# POWER.net
KiCad netlist of a schematic drawn in Altium Designer
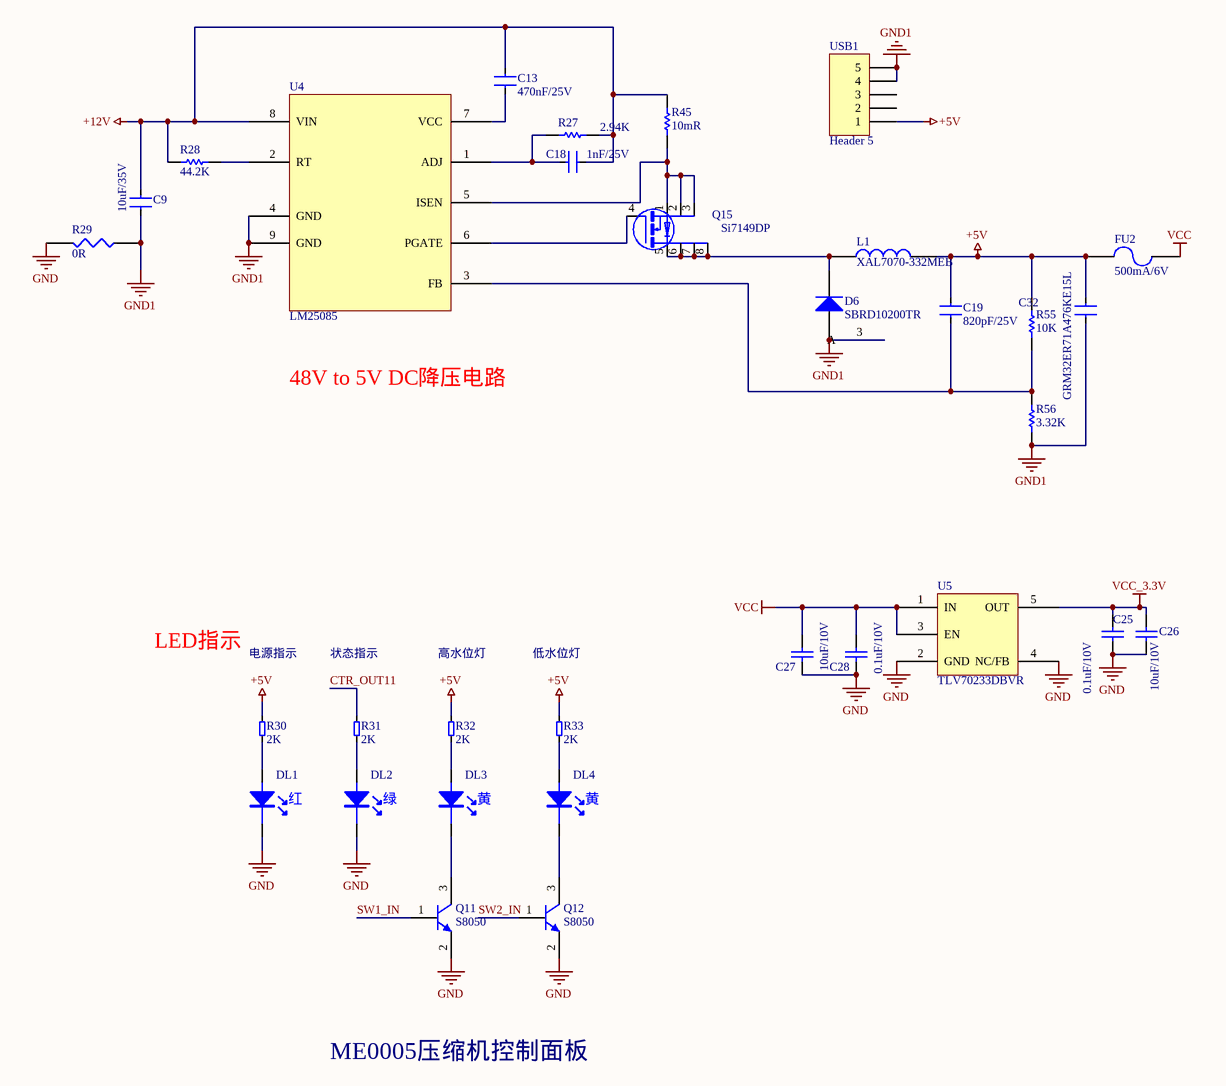
[diagram p0: POWER.SchDoc]

(export (version "E")
  (design (tool "Eeschema 10.0.6"))
  (components
    (comp (ref "C9")
      (value "10uF/35V")
      (footprint "1210C")
      (description "CCX85-103")
      (libsource (lib "无极性电容") (part "0.01UF"))
    )
    (comp (ref "C13")
      (value "470nF/25V")
      (footprint "0603C")
      (description "CCX85-103")
      (libsource (lib "无极性电容") (part "0.01UF"))
    )
    (comp (ref "C18")
      (value "1nF/25V")
      (footprint "0603C")
      (description "CCX85-103")
      (libsource (lib "无极性电容") (part "0.01UF"))
    )
    (comp (ref "C19")
      (value "820pF/25V")
      (footprint "0603C")
      (description "CCX85-103")
      (libsource (lib "无极性电容") (part "0.01UF"))
    )
    (comp (ref "C25")
      (value "0.1uF/10V")
      (footprint "0603C")
      (description "Capacitor")
      (fields (field (name "PUBLISHER") "Altium Limited"))
      (libsource (lib "Miscellaneous Devices") (part "Cap"))
    )
    (comp (ref "C26")
      (value "10uF/10V")
      (footprint "0603C")
      (description "Capacitor")
      (fields (field (name "PUBLISHER") "Altium Limited"))
      (libsource (lib "Miscellaneous Devices") (part "Cap"))
    )
    (comp (ref "C27")
      (value "10uF/10V")
      (footprint "0603C")
      (description "Capacitor")
      (fields (field (name "PUBLISHER") "Altium Limited"))
      (libsource (lib "Miscellaneous Devices") (part "Cap"))
    )
    (comp (ref "C28")
      (value "0.1uF/10V")
      (footprint "0603C")
      (description "Capacitor")
      (fields (field (name "PUBLISHER") "Altium Limited"))
      (libsource (lib "Miscellaneous Devices") (part "Cap"))
    )
    (comp (ref "C32")
      (value "GRM32ER71A476KE15L")
      (footprint "1210C")
      (description "CCX85-103")
      (libsource (lib "无极性电容") (part "0.01UF"))
    )
    (comp (ref "D6")
      (value "SBRD10200TR")
      (footprint "TO228P970-3N")
      (description "Default Diode")
      (fields (field (name "PUBLISHER") "Altium Limited"))
      (libsource (lib "SM") (part "Diode_2"))
    )
    (comp (ref "DL1")
      (value "红")
      (footprint "LED-3")
      (description "CP-L-7113SRD-D")
      (libsource (lib "光电器件") (part "L-7113SRD-D"))
    )
    (comp (ref "DL2")
      (value "绿")
      (footprint "LED-3")
      (description "CP-L-7113SRD-D")
      (libsource (lib "光电器件") (part "L-7113SRD-D"))
    )
    (comp (ref "DL3")
      (value "黄")
      (footprint "LED-3")
      (description "CP-L-7113SRD-D")
      (libsource (lib "光电器件") (part "L-7113SRD-D"))
    )
    (comp (ref "DL4")
      (value "黄")
      (footprint "LED-3")
      (description "CP-L-7113SRD-D")
      (libsource (lib "光电器件") (part "L-7113SRD-D"))
    )
    (comp (ref "FU2")
      (value "500mA/6V")
      (footprint "F0805")
      (description "Fuse")
      (libsource (lib "SM") (part "FUSE2"))
    )
    (comp (ref "L1") (value "XAL7070-332MEB") (footprint "XAL7070") (libsource (lib "*") (part "INDUCTOR")))
    (comp (ref "Q11")
      (value "S8050")
      (footprint "SOT23-3")
      (description "NPN Bipolar Transistor")
      (fields (field (name "PUBLISHER") "Altium Limited"))
      (libsource (lib "Miscellaneous Devices") (part "NPN"))
    )
    (comp (ref "Q12")
      (value "S8050")
      (footprint "SOT23-3")
      (description "NPN Bipolar Transistor")
      (fields (field (name "PUBLISHER") "Altium Limited"))
      (libsource (lib "Miscellaneous Devices") (part "NPN"))
    )
    (comp (ref "Q15")
      (value "Si7149DP")
      (footprint "PowerPAK SO-8")
      (description "Si4004DY")
      (libsource (lib "Schlib_20110825") (part "Si4004DY"))
    )
    (comp (ref "R27")
      (value "2.94K")
      (footprint "0603R")
      (description "Semiconductor Resistor")
      (fields (field (name "PUBLISHER") "Altium Limited"))
      (libsource (lib "Miscellaneous Devices") (part "Res Semi"))
    )
    (comp (ref "R28")
      (value "44.2K")
      (footprint "0603R")
      (description "Semiconductor Resistor")
      (fields (field (name "PUBLISHER") "Altium Limited"))
      (libsource (lib "Miscellaneous Devices") (part "Res Semi"))
    )
    (comp (ref "R29") (value "0R") (footprint "0805R") (libsource (lib "其他电阻") (part "RES1")))
    (comp (ref "R30")
      (value "2K")
      (footprint "0805R")
      (description "CR85-102J")
      (libsource (lib "SMD电阻") (part "1K"))
    )
    (comp (ref "R31")
      (value "2K")
      (footprint "0805R")
      (description "CR85-102J")
      (libsource (lib "SMD电阻") (part "1K"))
    )
    (comp (ref "R32")
      (value "2K")
      (footprint "0805R")
      (description "CR85-102J")
      (libsource (lib "SMD电阻") (part "1K"))
    )
    (comp (ref "R33")
      (value "2K")
      (footprint "0805R")
      (description "CR85-102J")
      (libsource (lib "SMD电阻") (part "1K"))
    )
    (comp (ref "R45")
      (value "10mR")
      (footprint "1206R")
      (description "Semiconductor Resistor")
      (fields (field (name "PUBLISHER") "Altium Limited"))
      (libsource (lib "Miscellaneous Devices") (part "Res Semi"))
    )
    (comp (ref "R55")
      (value "10K")
      (footprint "0603R")
      (description "Semiconductor Resistor")
      (fields (field (name "PUBLISHER") "Altium Limited"))
      (libsource (lib "Miscellaneous Devices") (part "Res Semi"))
    )
    (comp (ref "R56")
      (value "3.32K")
      (footprint "0603R")
      (description "Semiconductor Resistor")
      (fields (field (name "PUBLISHER") "Altium Limited"))
      (libsource (lib "Miscellaneous Devices") (part "Res Semi"))
    )
    (comp (ref "U4")
      (value "LM25085")
      (footprint "SOP65P490X265_HS-8N")
      (libsource (lib "Schlib_20110825") (part "LM25085"))
    )
    (comp (ref "U5")
      (value "TLV70233DBVR")
      (footprint "SOT23-5(DBV)")
      (libsource (lib "Schlib_20110825") (part "TLV70230DBVR"))
    )
    (comp (ref "USB1")
      (value "Header 5")
      (footprint "USB-A")
      (description "Header, 5-Pin")
      (fields (field (name "PUBLISHER") "Altium Limited"))
      (libsource (lib "Miscellaneous Connectors") (part "Header 5"))
    )
  )
  (nets
    (net (code "1") (name "+5V") (class "Default")
      (node (ref "C19") (pin "1") (pinfunction "1_1") (pintype "passive"))
      (node (ref "C32") (pin "1") (pinfunction "1_1") (pintype "passive"))
      (node (ref "FU2") (pin "1") (pinfunction "1_1") (pintype "passive"))
      (node (ref "L1") (pin "2") (pinfunction "2_2") (pintype "passive"))
      (node (ref "R30") (pin "2") (pinfunction "2_2") (pintype "passive"))
      (node (ref "R32") (pin "2") (pinfunction "2_2") (pintype "passive"))
      (node (ref "R33") (pin "2") (pinfunction "2_2") (pintype "passive"))
      (node (ref "R55") (pin "1") (pinfunction "1_1") (pintype "passive"))
      (node (ref "USB1") (pin "1") (pinfunction "1_1") (pintype "passive"))
    )
    (net (code "2") (name "+12V") (class "Default")
      (node (ref "C13") (pin "2") (pinfunction "2_2") (pintype "passive"))
      (node (ref "C18") (pin "1") (pinfunction "1_1") (pintype "passive"))
      (node (ref "C9") (pin "1") (pinfunction "1_1") (pintype "passive"))
      (node (ref "R27") (pin "1") (pinfunction "1_1") (pintype "passive"))
      (node (ref "R28") (pin "2") (pinfunction "2_2") (pintype "passive"))
      (node (ref "R45") (pin "1") (pinfunction "1_1") (pintype "passive"))
      (node (ref "U4") (pin "8") (pinfunction "VIN_8") (pintype "passive"))
    )
    (net (code "3") (name "/CTR_OUT11") (class "Default")
      (node (ref "R31") (pin "2") (pinfunction "2_2") (pintype "passive"))
    )
    (net (code "4") (name "/SW1_IN") (class "Default")
      (node (ref "Q11") (pin "1") (pinfunction "B_1") (pintype "passive"))
    )
    (net (code "5") (name "/SW2_IN") (class "Default")
      (node (ref "Q12") (pin "1") (pinfunction "B_1") (pintype "passive"))
    )
    (net (code "6") (name "GND") (class "Default")
      (node (ref "C25") (pin "2") (pinfunction "2_2") (pintype "passive"))
      (node (ref "C26") (pin "1") (pinfunction "1_1") (pintype "passive"))
      (node (ref "C27") (pin "1") (pinfunction "1_1") (pintype "passive"))
      (node (ref "C28") (pin "2") (pinfunction "2_2") (pintype "passive"))
      (node (ref "DL1") (pin "K") (pinfunction "2_K") (pintype "passive"))
      (node (ref "DL2") (pin "K") (pinfunction "2_K") (pintype "passive"))
      (node (ref "Q11") (pin "2") (pinfunction "E_2") (pintype "passive"))
      (node (ref "Q12") (pin "2") (pinfunction "E_2") (pintype "passive"))
      (node (ref "R29") (pin "2") (pinfunction "2_2") (pintype "passive"))
      (node (ref "U5") (pin "2") (pinfunction "GND_2") (pintype "passive"))
      (node (ref "U5") (pin "4") (pinfunction "NC/FB_4") (pintype "passive"))
    )
    (net (code "7") (name "GND1") (class "Default")
      (node (ref "C32") (pin "2") (pinfunction "2_2") (pintype "passive"))
      (node (ref "C9") (pin "2") (pinfunction "2_2") (pintype "passive"))
      (node (ref "D6") (pin "1") (pinfunction "A_1") (pintype "passive"))
      (node (ref "D6") (pin "3") (pinfunction "A_3") (pintype "passive"))
      (node (ref "R29") (pin "1") (pinfunction "1_1") (pintype "passive"))
      (node (ref "R56") (pin "2") (pinfunction "2_2") (pintype "passive"))
      (node (ref "U4") (pin "4") (pinfunction "GND_4") (pintype "passive"))
      (node (ref "U4") (pin "9") (pinfunction "GND_9") (pintype "passive"))
      (node (ref "USB1") (pin "4") (pinfunction "4_4") (pintype "passive"))
      (node (ref "USB1") (pin "5") (pinfunction "5_5") (pintype "passive"))
    )
    (net (code "8") (name "Net-(D6-K)") (class "Default")
      (node (ref "D6") (pin "2") (pinfunction "K_2") (pintype "passive"))
      (node (ref "L1") (pin "1") (pinfunction "1_1") (pintype "passive"))
      (node (ref "Q15") (pin "5") (pinfunction "D_5") (pintype "passive"))
      (node (ref "Q15") (pin "6") (pinfunction "D_6") (pintype "passive"))
      (node (ref "Q15") (pin "7") (pinfunction "D_7") (pintype "passive"))
      (node (ref "Q15") (pin "8") (pinfunction "D_8") (pintype "passive"))
    )
    (net (code "9") (name "Net-(DL1-1)") (class "Default")
      (node (ref "DL1") (pin "A") (pinfunction "1_A") (pintype "passive"))
      (node (ref "R30") (pin "1") (pinfunction "1_1") (pintype "passive"))
    )
    (net (code "10") (name "Net-(DL2-1)") (class "Default")
      (node (ref "DL2") (pin "A") (pinfunction "1_A") (pintype "passive"))
      (node (ref "R31") (pin "1") (pinfunction "1_1") (pintype "passive"))
    )
    (net (code "11") (name "Net-(DL3-1)") (class "Default")
      (node (ref "DL3") (pin "A") (pinfunction "1_A") (pintype "passive"))
      (node (ref "R32") (pin "1") (pinfunction "1_1") (pintype "passive"))
    )
    (net (code "12") (name "Net-(DL3-2)") (class "Default")
      (node (ref "DL3") (pin "K") (pinfunction "2_K") (pintype "passive"))
      (node (ref "Q11") (pin "3") (pinfunction "C_3") (pintype "passive"))
    )
    (net (code "13") (name "Net-(DL4-1)") (class "Default")
      (node (ref "DL4") (pin "A") (pinfunction "1_A") (pintype "passive"))
      (node (ref "R33") (pin "1") (pinfunction "1_1") (pintype "passive"))
    )
    (net (code "14") (name "Net-(DL4-2)") (class "Default")
      (node (ref "DL4") (pin "K") (pinfunction "2_K") (pintype "passive"))
      (node (ref "Q12") (pin "3") (pinfunction "C_3") (pintype "passive"))
    )
    (net (code "15") (name "Net-(Q15-G)") (class "Default")
      (node (ref "Q15") (pin "4") (pinfunction "G_4") (pintype "passive"))
      (node (ref "U4") (pin "6") (pinfunction "PGATE_6") (pintype "passive"))
    )
    (net (code "16") (name "Net-(U4-ADJ)") (class "Default")
      (node (ref "C18") (pin "2") (pinfunction "2_2") (pintype "passive"))
      (node (ref "R27") (pin "2") (pinfunction "2_2") (pintype "passive"))
      (node (ref "U4") (pin "1") (pinfunction "ADJ_1") (pintype "passive"))
    )
    (net (code "17") (name "Net-(U4-FB)") (class "Default")
      (node (ref "C19") (pin "2") (pinfunction "2_2") (pintype "passive"))
      (node (ref "R55") (pin "2") (pinfunction "2_2") (pintype "passive"))
      (node (ref "R56") (pin "1") (pinfunction "1_1") (pintype "passive"))
      (node (ref "U4") (pin "3") (pinfunction "FB_3") (pintype "passive"))
    )
    (net (code "18") (name "Net-(U4-ISEN)") (class "Default")
      (node (ref "Q15") (pin "1") (pinfunction "S_1") (pintype "passive"))
      (node (ref "Q15") (pin "2") (pinfunction "S_2") (pintype "passive"))
      (node (ref "Q15") (pin "3") (pinfunction "S_3") (pintype "passive"))
      (node (ref "R45") (pin "2") (pinfunction "2_2") (pintype "passive"))
      (node (ref "U4") (pin "5") (pinfunction "ISEN_5") (pintype "passive"))
    )
    (net (code "19") (name "Net-(U4-RT)") (class "Default")
      (node (ref "R28") (pin "1") (pinfunction "1_1") (pintype "passive"))
      (node (ref "U4") (pin "2") (pinfunction "RT_2") (pintype "passive"))
    )
    (net (code "20") (name "Net-(U4-VCC)") (class "Default")
      (node (ref "C13") (pin "1") (pinfunction "1_1") (pintype "passive"))
      (node (ref "U4") (pin "7") (pinfunction "VCC_7") (pintype "passive"))
    )
    (net (code "21") (name "VCC") (class "Default")
      (node (ref "C27") (pin "2") (pinfunction "2_2") (pintype "passive"))
      (node (ref "C28") (pin "1") (pinfunction "1_1") (pintype "passive"))
      (node (ref "FU2") (pin "2") (pinfunction "2_2") (pintype "passive"))
      (node (ref "U5") (pin "1") (pinfunction "IN_1") (pintype "passive"))
      (node (ref "U5") (pin "3") (pinfunction "EN_3") (pintype "passive"))
    )
    (net (code "22") (name "VCC_3.3V") (class "Default")
      (node (ref "C25") (pin "1") (pinfunction "1_1") (pintype "passive"))
      (node (ref "C26") (pin "2") (pinfunction "2_2") (pintype "passive"))
      (node (ref "U5") (pin "5") (pinfunction "OUT_5") (pintype "passive"))
    )
    (net (code "23") (name "unconnected-(USB1-Pad2)") (class "Default")
      (node (ref "USB1") (pin "2") (pinfunction "2_2") (pintype "passive"))
    )
    (net (code "24") (name "unconnected-(USB1-Pad3)") (class "Default")
      (node (ref "USB1") (pin "3") (pinfunction "3_3") (pintype "passive"))
    )
  )
)
